# ignition3.net
KiCad netlist of a schematic drawn in EAGLE
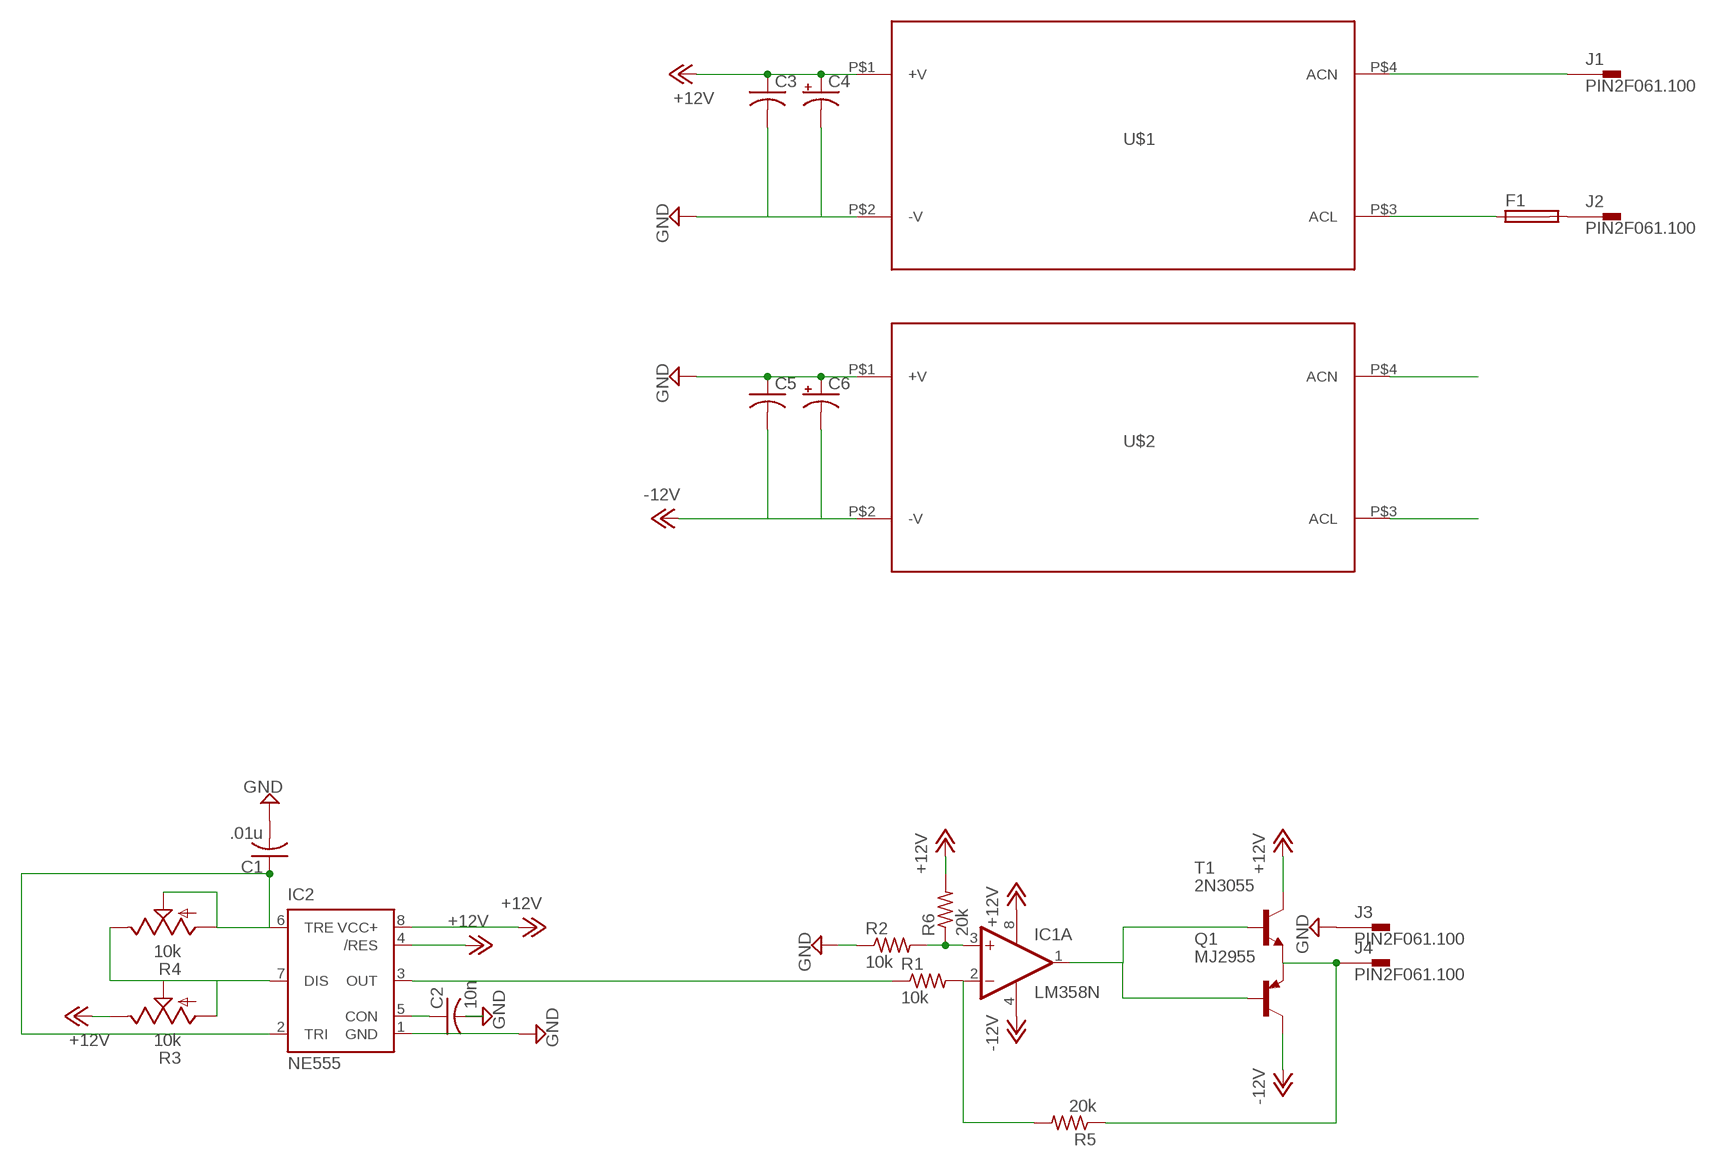
[diagram p0: schematic, sheet 1]

(export (version "E")
  (design (tool "Eeschema 10.0.6"))
  (components
    (comp (ref "C1")
      (value ".01u")
      (footprint "eagle-import:C050-035X075")
      (libsource (lib "eagle-import") (part "C-US050-035X075"))
    )
    (comp (ref "C2")
      (value "10n")
      (footprint "eagle-import:C075-042X103")
      (libsource (lib "eagle-import") (part "C-US075-042X103"))
    )
    (comp (ref "C3")
      (value "C-US050-035X075")
      (footprint "eagle-import:C050-035X075")
      (libsource (lib "eagle-import") (part "C-US050-035X075"))
    )
    (comp (ref "C4")
      (value "CPOL-USE5-5")
      (footprint "eagle-import:E5-5")
      (libsource (lib "eagle-import") (part "CPOL-USE5-5"))
    )
    (comp (ref "C5")
      (value "C-US050-035X075")
      (footprint "eagle-import:C050-035X075")
      (libsource (lib "eagle-import") (part "C-US050-035X075"))
    )
    (comp (ref "C6")
      (value "CPOL-USE5-5")
      (footprint "eagle-import:E5-5")
      (libsource (lib "eagle-import") (part "CPOL-USE5-5"))
    )
    (comp (ref "F1")
      (value "SH25")
      (footprint "eagle-import:SH25")
      (fields (field (name "MF") "SCHURTER") (field (name "MPN") "0031.8211"))
      (libsource (lib "eagle-import") (part "SH25"))
    )
    (comp (ref "IC1")
      (value "LM358N")
      (footprint "eagle-import:DIL08")
      (libsource (lib "eagle-import") (part "LM358N"))
    )
    (comp (ref "IC2")
      (value "NE555")
      (footprint "eagle-import:DIL-08")
      (fields (field (name "MF") "Arrow Electronics") (field (name "MPN") "NE555N"))
      (libsource (lib "eagle-import") (part "NE555"))
    )
    (comp (ref "J1")
      (value "PIN2F061.100")
      (footprint "eagle-import:F061.100")
      (libsource (lib "eagle-import") (part "PIN2F061.100"))
    )
    (comp (ref "J2")
      (value "PIN2F061.100")
      (footprint "eagle-import:F061.100")
      (libsource (lib "eagle-import") (part "PIN2F061.100"))
    )
    (comp (ref "J3")
      (value "PIN2F061.100")
      (footprint "eagle-import:F061.100")
      (libsource (lib "eagle-import") (part "PIN2F061.100"))
    )
    (comp (ref "J4")
      (value "PIN2F061.100")
      (footprint "eagle-import:F061.100")
      (libsource (lib "eagle-import") (part "PIN2F061.100"))
    )
    (comp (ref "Q1")
      (value "MJ2955")
      (footprint "eagle-import:TO3")
      (libsource (lib "eagle-import") (part "MJ2955"))
    )
    (comp (ref "R1")
      (value "10k")
      (footprint "eagle-import:0207_10")
      (libsource (lib "eagle-import") (part "R-US_0207/10"))
    )
    (comp (ref "R2")
      (value "10k")
      (footprint "eagle-import:0207_10")
      (libsource (lib "eagle-import") (part "R-US_0207/10"))
    )
    (comp (ref "R3")
      (value "10k")
      (footprint "eagle-import:B64Y")
      (libsource (lib "eagle-import") (part "TRIM_US-B64Y"))
    )
    (comp (ref "R4")
      (value "10k")
      (footprint "eagle-import:B64Y")
      (libsource (lib "eagle-import") (part "TRIM_US-B64Y"))
    )
    (comp (ref "R5")
      (value "20k")
      (footprint "eagle-import:0207_10")
      (libsource (lib "eagle-import") (part "R-US_0207/10"))
    )
    (comp (ref "R6")
      (value "20k")
      (footprint "eagle-import:0207_10")
      (libsource (lib "eagle-import") (part "R-US_0207/10"))
    )
    (comp (ref "T1")
      (value "2N3055")
      (footprint "eagle-import:TO3")
      (libsource (lib "eagle-import") (part "2N3055"))
    )
    (comp (ref "U$1")
      (value "IRM-60-12")
      (footprint "eagle-import:IRM-60-12")
      (libsource (lib "eagle-import") (part "IRM-60-12"))
    )
    (comp (ref "U$2")
      (value "IRM-60-12")
      (footprint "eagle-import:IRM-60-12")
      (libsource (lib "eagle-import") (part "IRM-60-12"))
    )
  )
  (nets
    (net (code "1") (name "+12V") (class "Default")
      (node (ref "C3") (pin "1") (pinfunction "1_1") (pintype "passive"))
      (node (ref "C4") (pin "+") (pinfunction "+_+") (pintype "passive"))
      (node (ref "IC1") (pin "8") (pinfunction "V+_8") (pintype "power_in"))
      (node (ref "IC2") (pin "4") (pinfunction "/RES_4") (pintype "input"))
      (node (ref "IC2") (pin "8") (pinfunction "VCC+_8") (pintype "power_in"))
      (node (ref "R3") (pin "E") (pinfunction "E_E") (pintype "passive"))
      (node (ref "R6") (pin "2") (pinfunction "2_2") (pintype "passive"))
      (node (ref "T1") (pin "C") (pinfunction "C_C") (pintype "passive"))
      (node (ref "T1") (pin "C/") (pinfunction "C_C/") (pintype "passive"))
      (node (ref "U$1") (pin "P$1") (pinfunction "+V_P$1") (pintype "bidirectional"))
    )
    (net (code "2") (name "-12V") (class "Default")
      (node (ref "C5") (pin "2") (pinfunction "2_2") (pintype "passive"))
      (node (ref "C6") (pin "-") (pinfunction "-_-") (pintype "passive"))
      (node (ref "IC1") (pin "4") (pinfunction "V-_4") (pintype "power_in"))
      (node (ref "Q1") (pin "C") (pinfunction "C_C") (pintype "passive"))
      (node (ref "Q1") (pin "C/") (pinfunction "C_C/") (pintype "passive"))
      (node (ref "U$2") (pin "P$2") (pinfunction "-V_P$2") (pintype "bidirectional"))
    )
    (net (code "3") (name "/L") (class "Default")
      (node (ref "F1") (pin "1") (pinfunction "1_1") (pintype "passive"))
      (node (ref "U$1") (pin "P$3") (pinfunction "ACL_P$3") (pintype "bidirectional"))
      (node (ref "U$2") (pin "P$3") (pinfunction "ACL_P$3") (pintype "bidirectional"))
    )
    (net (code "4") (name "/N") (class "Default")
      (node (ref "J1") (pin "A1") (pinfunction "1_A1") (pintype "passive"))
      (node (ref "J1") (pin "A2") (pinfunction "1_A2") (pintype "passive"))
      (node (ref "U$1") (pin "P$4") (pinfunction "ACN_P$4") (pintype "bidirectional"))
      (node (ref "U$2") (pin "P$4") (pinfunction "ACN_P$4") (pintype "bidirectional"))
    )
    (net (code "5") (name "GND") (class "Default")
      (node (ref "C1") (pin "2") (pinfunction "2_2") (pintype "passive"))
      (node (ref "C2") (pin "2") (pinfunction "2_2") (pintype "passive"))
      (node (ref "C3") (pin "2") (pinfunction "2_2") (pintype "passive"))
      (node (ref "C4") (pin "-") (pinfunction "-_-") (pintype "passive"))
      (node (ref "C5") (pin "1") (pinfunction "1_1") (pintype "passive"))
      (node (ref "C6") (pin "+") (pinfunction "+_+") (pintype "passive"))
      (node (ref "IC2") (pin "1") (pinfunction "GND_1") (pintype "power_in"))
      (node (ref "J3") (pin "A1") (pinfunction "1_A1") (pintype "passive"))
      (node (ref "J3") (pin "A2") (pinfunction "1_A2") (pintype "passive"))
      (node (ref "R2") (pin "1") (pinfunction "1_1") (pintype "passive"))
      (node (ref "U$1") (pin "P$2") (pinfunction "-V_P$2") (pintype "bidirectional"))
      (node (ref "U$2") (pin "P$1") (pinfunction "+V_P$1") (pintype "bidirectional"))
    )
    (net (code "6") (name "Net-(F1-Pad2)") (class "Default")
      (node (ref "F1") (pin "2") (pinfunction "2_2") (pintype "passive"))
      (node (ref "J2") (pin "A1") (pinfunction "1_A1") (pintype "passive"))
      (node (ref "J2") (pin "A2") (pinfunction "1_A2") (pintype "passive"))
    )
    (net (code "7") (name "Net-(IC1A-+IN)") (class "Default")
      (node (ref "IC1") (pin "3") (pinfunction "+IN_3") (pintype "input"))
      (node (ref "R2") (pin "2") (pinfunction "2_2") (pintype "passive"))
      (node (ref "R6") (pin "1") (pinfunction "1_1") (pintype "passive"))
    )
    (net (code "8") (name "Net-(IC1A--IN)") (class "Default")
      (node (ref "IC1") (pin "2") (pinfunction "-IN_2") (pintype "input"))
      (node (ref "R1") (pin "2") (pinfunction "2_2") (pintype "passive"))
      (node (ref "R5") (pin "2") (pinfunction "2_2") (pintype "passive"))
    )
    (net (code "9") (name "Net-(IC1A-OUT)") (class "Default")
      (node (ref "IC1") (pin "1") (pinfunction "OUT_1") (pintype "output"))
      (node (ref "Q1") (pin "B") (pinfunction "B_B") (pintype "passive"))
      (node (ref "T1") (pin "B") (pinfunction "B_B") (pintype "passive"))
    )
    (net (code "10") (name "Net-(IC2-CON)") (class "Default")
      (node (ref "C2") (pin "1") (pinfunction "1_1") (pintype "passive"))
      (node (ref "IC2") (pin "5") (pinfunction "CON_5") (pintype "input"))
    )
    (net (code "11") (name "Net-(IC2-DIS)") (class "Default")
      (node (ref "IC2") (pin "7") (pinfunction "DIS_7") (pintype "input"))
      (node (ref "R3") (pin "A") (pinfunction "A_A") (pintype "passive"))
      (node (ref "R3") (pin "S") (pinfunction "S_S") (pintype "passive"))
      (node (ref "R4") (pin "E") (pinfunction "E_E") (pintype "passive"))
    )
    (net (code "12") (name "Net-(IC2-OUT)") (class "Default")
      (node (ref "IC2") (pin "3") (pinfunction "OUT_3") (pintype "output"))
      (node (ref "R1") (pin "1") (pinfunction "1_1") (pintype "passive"))
    )
    (net (code "13") (name "Net-(IC2-TRE)") (class "Default")
      (node (ref "C1") (pin "1") (pinfunction "1_1") (pintype "passive"))
      (node (ref "IC2") (pin "2") (pinfunction "TRI_2") (pintype "input"))
      (node (ref "IC2") (pin "6") (pinfunction "TRE_6") (pintype "input"))
      (node (ref "R4") (pin "A") (pinfunction "A_A") (pintype "passive"))
      (node (ref "R4") (pin "S") (pinfunction "S_S") (pintype "passive"))
    )
    (net (code "14") (name "Net-(J4-1-PadA1)") (class "Default")
      (node (ref "J4") (pin "A1") (pinfunction "1_A1") (pintype "passive"))
      (node (ref "J4") (pin "A2") (pinfunction "1_A2") (pintype "passive"))
      (node (ref "Q1") (pin "E") (pinfunction "E_E") (pintype "passive"))
      (node (ref "R5") (pin "1") (pinfunction "1_1") (pintype "passive"))
      (node (ref "T1") (pin "E") (pinfunction "E_E") (pintype "passive"))
    )
  )
)
